# Nusbio_Flash_Extension.net
KiCad netlist of a schematic drawn in EAGLE
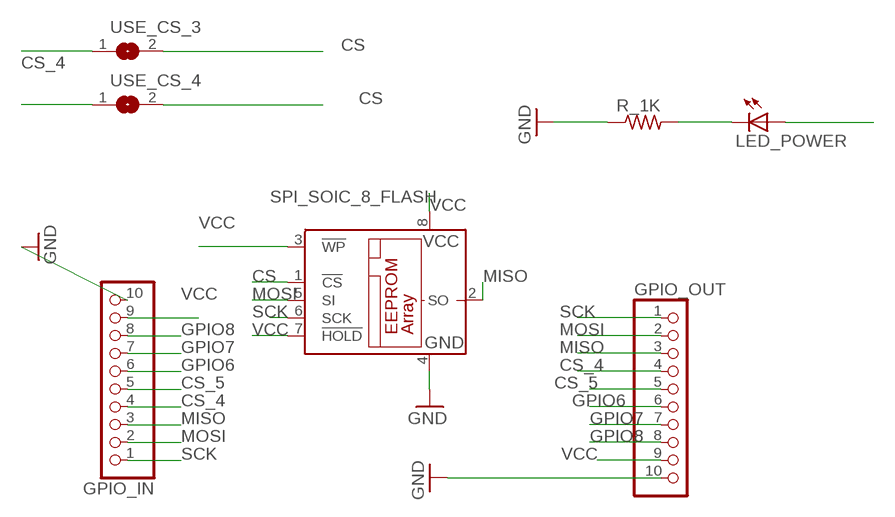
[diagram p0: schematic, sheet 1]

(export (version "E")
  (design (tool "Eeschema 10.0.6"))
  (components
    (comp (ref "GPIO_IN")
      (value "PINHD-1X10")
      (footprint "eagle-import:1X10-BIG")
      (libsource (lib "eagle-import") (part "PINHD-1X10"))
    )
    (comp (ref "GPIO_OUT")
      (value "PINHD-1X10")
      (footprint "eagle-import:1X10-BIG")
      (libsource (lib "eagle-import") (part "PINHD-1X10"))
    )
    (comp (ref "LED_POWER")
      (value "LEDSMT1206")
      (footprint "eagle-import:1206")
      (libsource (lib "eagle-import") (part "LEDSMT1206"))
    )
    (comp (ref "R_1K")
      (value "R-US_R1206")
      (footprint "eagle-import:R1206")
      (libsource (lib "eagle-import") (part "R-US_R1206"))
    )
    (comp (ref "SPI_SOIC_8_FLASH")
      (value "25AA080SN")
      (footprint "eagle-import:SO-08")
      (fields (field (name "MF") "MICROCHIP") (field (name "MPN") "25AA080/SN"))
      (libsource (lib "eagle-import") (part "25SNAA080"))
    )
    (comp (ref "USE_CS_3")
      (value "SOLDERJUMPERREFLOW")
      (footprint "eagle-import:SOLDERJUMPER_REFLOW")
      (libsource (lib "eagle-import") (part "SOLDERJUMPERREFLOW"))
    )
    (comp (ref "USE_CS_4")
      (value "SOLDERJUMPERREFLOW")
      (footprint "eagle-import:SOLDERJUMPER_REFLOW")
      (libsource (lib "eagle-import") (part "SOLDERJUMPERREFLOW"))
    )
  )
  (nets
    (net (code "1") (name "/CS") (class "Default")
      (node (ref "SPI_SOIC_8_FLASH") (pin "1") (pinfunction "~{CS}_1") (pintype "input"))
      (node (ref "USE_CS_3") (pin "2") (pinfunction "2_2") (pintype "passive"))
      (node (ref "USE_CS_4") (pin "2") (pinfunction "2_2") (pintype "passive"))
    )
    (net (code "2") (name "/CS_4") (class "Default")
      (node (ref "GPIO_IN") (pin "4") (pinfunction "4_4") (pintype "passive"))
      (node (ref "GPIO_OUT") (pin "4") (pinfunction "4_4") (pintype "passive"))
      (node (ref "USE_CS_3") (pin "1") (pinfunction "1_1") (pintype "passive"))
    )
    (net (code "3") (name "/CS_5") (class "Default")
      (node (ref "GPIO_IN") (pin "5") (pinfunction "5_5") (pintype "passive"))
      (node (ref "GPIO_OUT") (pin "5") (pinfunction "5_5") (pintype "passive"))
      (node (ref "USE_CS_4") (pin "1") (pinfunction "1_1") (pintype "passive"))
    )
    (net (code "4") (name "/GPIO6") (class "Default")
      (node (ref "GPIO_IN") (pin "6") (pinfunction "6_6") (pintype "passive"))
      (node (ref "GPIO_OUT") (pin "6") (pinfunction "6_6") (pintype "passive"))
    )
    (net (code "5") (name "/GPIO7") (class "Default")
      (node (ref "GPIO_IN") (pin "7") (pinfunction "7_7") (pintype "passive"))
      (node (ref "GPIO_OUT") (pin "7") (pinfunction "7_7") (pintype "passive"))
    )
    (net (code "6") (name "/GPIO8") (class "Default")
      (node (ref "GPIO_IN") (pin "8") (pinfunction "8_8") (pintype "passive"))
      (node (ref "GPIO_OUT") (pin "8") (pinfunction "8_8") (pintype "passive"))
    )
    (net (code "7") (name "/MISO") (class "Default")
      (node (ref "GPIO_IN") (pin "3") (pinfunction "3_3") (pintype "passive"))
      (node (ref "GPIO_OUT") (pin "3") (pinfunction "3_3") (pintype "passive"))
      (node (ref "SPI_SOIC_8_FLASH") (pin "2") (pinfunction "SO_2") (pintype "bidirectional"))
    )
    (net (code "8") (name "/MOSI") (class "Default")
      (node (ref "GPIO_IN") (pin "2") (pinfunction "2_2") (pintype "passive"))
      (node (ref "GPIO_OUT") (pin "2") (pinfunction "2_2") (pintype "passive"))
      (node (ref "SPI_SOIC_8_FLASH") (pin "5") (pinfunction "SI_5") (pintype "input"))
    )
    (net (code "9") (name "/SCK") (class "Default")
      (node (ref "GPIO_IN") (pin "1") (pinfunction "1_1") (pintype "passive"))
      (node (ref "GPIO_OUT") (pin "1") (pinfunction "1_1") (pintype "passive"))
      (node (ref "SPI_SOIC_8_FLASH") (pin "6") (pinfunction "SCK_6") (pintype "input"))
    )
    (net (code "10") (name "/VCC") (class "Default")
      (node (ref "GPIO_IN") (pin "9") (pinfunction "9_9") (pintype "passive"))
      (node (ref "GPIO_OUT") (pin "9") (pinfunction "9_9") (pintype "passive"))
      (node (ref "LED_POWER") (pin "A") (pinfunction "A_A") (pintype "passive"))
      (node (ref "SPI_SOIC_8_FLASH") (pin "3") (pinfunction "~{WP}_3") (pintype "input"))
      (node (ref "SPI_SOIC_8_FLASH") (pin "7") (pinfunction "~{HOLD}_7") (pintype "input"))
      (node (ref "SPI_SOIC_8_FLASH") (pin "8") (pinfunction "VCC_8") (pintype "power_in"))
    )
    (net (code "11") (name "GND") (class "Default")
      (node (ref "GPIO_IN") (pin "10") (pinfunction "10_10") (pintype "passive"))
      (node (ref "GPIO_OUT") (pin "10") (pinfunction "10_10") (pintype "passive"))
      (node (ref "R_1K") (pin "1") (pinfunction "1_1") (pintype "passive"))
      (node (ref "SPI_SOIC_8_FLASH") (pin "4") (pinfunction "GND_4") (pintype "power_in"))
    )
    (net (code "12") (name "Net-(LED_POWER-PadC)") (class "Default")
      (node (ref "LED_POWER") (pin "C") (pinfunction "C_C") (pintype "passive"))
      (node (ref "R_1K") (pin "2") (pinfunction "2_2") (pintype "passive"))
    )
  )
)
